# ramanPi_interfaceBoard.net
KiCad netlist of a schematic drawn in EAGLE
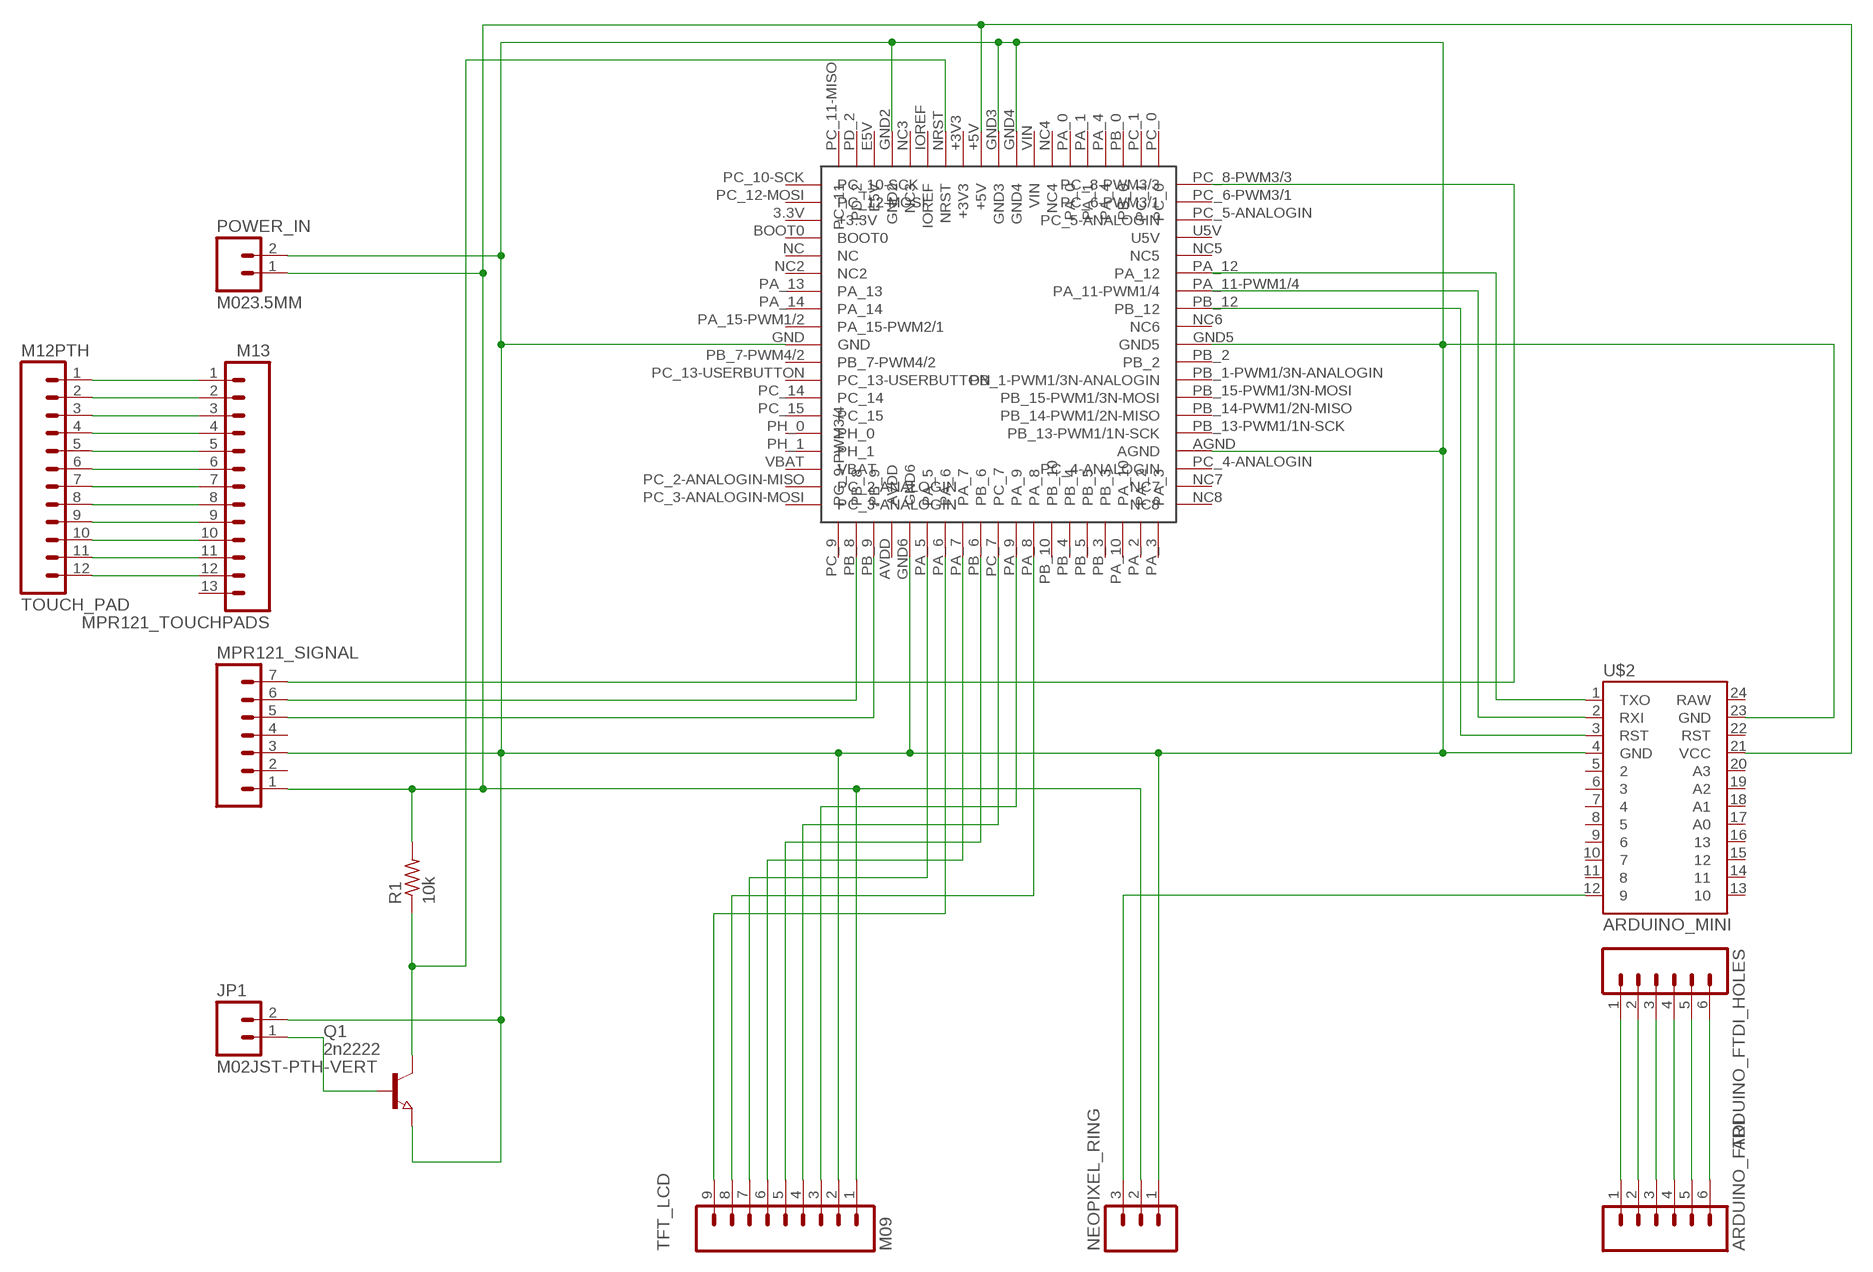
[diagram p0: schematic, sheet 1]

(export (version "E")
  (design (tool "Eeschema 10.0.6"))
  (components
    (comp (ref "ARDUINO_FTDI")
      (value "M06SIP")
      (footprint "eagle-import:1X06")
      (libsource (lib "eagle-import") (part "M06SIP"))
    )
    (comp (ref "ARDUINO_FTDI_HOLES")
      (value "M06SIP")
      (footprint "eagle-import:1X06")
      (libsource (lib "eagle-import") (part "M06SIP"))
    )
    (comp (ref "JP1")
      (value "M02JST-PTH-VERT")
      (footprint "eagle-import:JST-2-PTH-VERT")
      (libsource (lib "eagle-import") (part "M02JST-PTH-VERT"))
    )
    (comp (ref "MPR121_SIGNAL")
      (value "M07")
      (footprint "eagle-import:1X07")
      (libsource (lib "eagle-import") (part "M07"))
    )
    (comp (ref "MPR121_TOUCHPADS")
      (value "M13")
      (footprint "eagle-import:1X13")
      (libsource (lib "eagle-import") (part "M13"))
    )
    (comp (ref "NEOPIXEL_RING")
      (value "M03JST-PTH-VERT")
      (footprint "eagle-import:JST-3-PTH-VERT")
      (libsource (lib "eagle-import") (part "M03JST-PTH-VERT"))
    )
    (comp (ref "POWER_IN")
      (value "M023.5MM")
      (footprint "eagle-import:SCREWTERMINAL-3.5MM-2")
      (libsource (lib "eagle-import") (part "M023.5MM"))
    )
    (comp (ref "Q1")
      (value "2n2222")
      (footprint "eagle-import:SOT23")
      (libsource (lib "eagle-import") (part "NPN-TRANSISTOR_SOT23"))
    )
    (comp (ref "R1")
      (value "10k")
      (footprint "eagle-import:M1206")
      (libsource (lib "eagle-import") (part "R-US_M1206"))
    )
    (comp (ref "TFT_LCD")
      (value "M09")
      (footprint "eagle-import:1X09")
      (libsource (lib "eagle-import") (part "M09"))
    )
    (comp (ref "TOUCH_PAD")
      (value "M12PTH")
      (footprint "eagle-import:1X12")
      (libsource (lib "eagle-import") (part "M12PTH"))
    )
    (comp (ref "U$1")
      (value "STNUCLEOF401RE")
      (footprint "eagle-import:F401-RE")
      (libsource (lib "eagle-import") (part "STNUCLEOF401RE"))
    )
    (comp (ref "U$2")
      (value "ARDUINO_MINI")
      (footprint "eagle-import:ARDUINO_MINI")
      (libsource (lib "eagle-import") (part "ARDUINO_MINI"))
    )
  )
  (nets
    (net (code "1") (name "/+3.3V") (class "Default")
      (node (ref "U$1") (pin "3.3V") (pinfunction "+3.3V_3.3V") (pintype "power_in"))
    )
    (net (code "2") (name "/+3V3") (class "Default")
      (node (ref "U$1") (pin "+3V3") (pinfunction "+3V3_+3V3") (pintype "power_in"))
    )
    (net (code "3") (name "/AVDD") (class "Default")
      (node (ref "U$1") (pin "AVDD") (pinfunction "AVDD_AVDD") (pintype "power_in"))
    )
    (net (code "4") (name "/E5V") (class "Default")
      (node (ref "U$1") (pin "E5V") (pinfunction "E5V_E5V") (pintype "power_in"))
    )
    (net (code "5") (name "/U5V") (class "Default")
      (node (ref "U$1") (pin "U5V") (pinfunction "U5V_U5V") (pintype "power_in"))
    )
    (net (code "6") (name "/VBAT") (class "Default")
      (node (ref "U$1") (pin "VBAT") (pinfunction "VBAT_VBAT") (pintype "power_in"))
    )
    (net (code "7") (name "/VIN") (class "Default")
      (node (ref "U$1") (pin "VIN") (pinfunction "VIN_VIN") (pintype "power_in"))
    )
    (net (code "8") (name "Net-(ARDUINO_FTDI-Pad1)") (class "Default")
      (node (ref "ARDUINO_FTDI") (pin "1") (pinfunction "1_1") (pintype "passive"))
      (node (ref "ARDUINO_FTDI_HOLES") (pin "1") (pinfunction "1_1") (pintype "passive"))
    )
    (net (code "9") (name "Net-(ARDUINO_FTDI-Pad2)") (class "Default")
      (node (ref "ARDUINO_FTDI") (pin "2") (pinfunction "2_2") (pintype "passive"))
      (node (ref "ARDUINO_FTDI_HOLES") (pin "2") (pinfunction "2_2") (pintype "passive"))
    )
    (net (code "10") (name "Net-(ARDUINO_FTDI-Pad3)") (class "Default")
      (node (ref "ARDUINO_FTDI") (pin "3") (pinfunction "3_3") (pintype "passive"))
      (node (ref "ARDUINO_FTDI_HOLES") (pin "3") (pinfunction "3_3") (pintype "passive"))
    )
    (net (code "11") (name "Net-(ARDUINO_FTDI-Pad4)") (class "Default")
      (node (ref "ARDUINO_FTDI") (pin "4") (pinfunction "4_4") (pintype "passive"))
      (node (ref "ARDUINO_FTDI_HOLES") (pin "4") (pinfunction "4_4") (pintype "passive"))
    )
    (net (code "12") (name "Net-(ARDUINO_FTDI-Pad5)") (class "Default")
      (node (ref "ARDUINO_FTDI") (pin "5") (pinfunction "5_5") (pintype "passive"))
      (node (ref "ARDUINO_FTDI_HOLES") (pin "5") (pinfunction "5_5") (pintype "passive"))
    )
    (net (code "13") (name "Net-(ARDUINO_FTDI-Pad6)") (class "Default")
      (node (ref "ARDUINO_FTDI") (pin "6") (pinfunction "6_6") (pintype "passive"))
      (node (ref "ARDUINO_FTDI_HOLES") (pin "6") (pinfunction "6_6") (pintype "passive"))
    )
    (net (code "14") (name "Net-(MPR121_SIGNAL-Pad5)") (class "Default")
      (node (ref "MPR121_SIGNAL") (pin "5") (pinfunction "5_5") (pintype "passive"))
      (node (ref "U$1") (pin "PB_9") (pinfunction "PB_9_PB_9") (pintype "bidirectional"))
    )
    (net (code "15") (name "Net-(MPR121_SIGNAL-Pad6)") (class "Default")
      (node (ref "MPR121_SIGNAL") (pin "6") (pinfunction "6_6") (pintype "passive"))
      (node (ref "U$1") (pin "PB_8") (pinfunction "PB_8_PB_8") (pintype "bidirectional"))
    )
    (net (code "16") (name "Net-(MPR121_SIGNAL-Pad7)") (class "Default")
      (node (ref "MPR121_SIGNAL") (pin "7") (pinfunction "7_7") (pintype "passive"))
      (node (ref "U$1") (pin "PC_8-PWM3/3") (pinfunction "PC_8-PWM3/3_PC_8-PWM3/3") (pintype "bidirectional"))
    )
    (net (code "17") (name "Net-(MPR121_TOUCHPADS-Pad1)") (class "Default")
      (node (ref "MPR121_TOUCHPADS") (pin "1") (pinfunction "1_1") (pintype "passive"))
      (node (ref "TOUCH_PAD") (pin "1") (pinfunction "1_1") (pintype "passive"))
    )
    (net (code "18") (name "Net-(MPR121_TOUCHPADS-Pad2)") (class "Default")
      (node (ref "MPR121_TOUCHPADS") (pin "2") (pinfunction "2_2") (pintype "passive"))
      (node (ref "TOUCH_PAD") (pin "2") (pinfunction "2_2") (pintype "passive"))
    )
    (net (code "19") (name "Net-(MPR121_TOUCHPADS-Pad3)") (class "Default")
      (node (ref "MPR121_TOUCHPADS") (pin "3") (pinfunction "3_3") (pintype "passive"))
      (node (ref "TOUCH_PAD") (pin "3") (pinfunction "3_3") (pintype "passive"))
    )
    (net (code "20") (name "Net-(MPR121_TOUCHPADS-Pad4)") (class "Default")
      (node (ref "MPR121_TOUCHPADS") (pin "4") (pinfunction "4_4") (pintype "passive"))
      (node (ref "TOUCH_PAD") (pin "4") (pinfunction "4_4") (pintype "passive"))
    )
    (net (code "21") (name "Net-(MPR121_TOUCHPADS-Pad5)") (class "Default")
      (node (ref "MPR121_TOUCHPADS") (pin "5") (pinfunction "5_5") (pintype "passive"))
      (node (ref "TOUCH_PAD") (pin "5") (pinfunction "5_5") (pintype "passive"))
    )
    (net (code "22") (name "Net-(MPR121_TOUCHPADS-Pad6)") (class "Default")
      (node (ref "MPR121_TOUCHPADS") (pin "6") (pinfunction "6_6") (pintype "passive"))
      (node (ref "TOUCH_PAD") (pin "6") (pinfunction "6_6") (pintype "passive"))
    )
    (net (code "23") (name "Net-(MPR121_TOUCHPADS-Pad7)") (class "Default")
      (node (ref "MPR121_TOUCHPADS") (pin "7") (pinfunction "7_7") (pintype "passive"))
      (node (ref "TOUCH_PAD") (pin "7") (pinfunction "7_7") (pintype "passive"))
    )
    (net (code "24") (name "Net-(MPR121_TOUCHPADS-Pad8)") (class "Default")
      (node (ref "MPR121_TOUCHPADS") (pin "8") (pinfunction "8_8") (pintype "passive"))
      (node (ref "TOUCH_PAD") (pin "8") (pinfunction "8_8") (pintype "passive"))
    )
    (net (code "25") (name "Net-(MPR121_TOUCHPADS-Pad9)") (class "Default")
      (node (ref "MPR121_TOUCHPADS") (pin "9") (pinfunction "9_9") (pintype "passive"))
      (node (ref "TOUCH_PAD") (pin "9") (pinfunction "9_9") (pintype "passive"))
    )
    (net (code "26") (name "Net-(MPR121_TOUCHPADS-Pad10)") (class "Default")
      (node (ref "MPR121_TOUCHPADS") (pin "10") (pinfunction "10_10") (pintype "passive"))
      (node (ref "TOUCH_PAD") (pin "10") (pinfunction "10_10") (pintype "passive"))
    )
    (net (code "27") (name "Net-(MPR121_TOUCHPADS-Pad11)") (class "Default")
      (node (ref "MPR121_TOUCHPADS") (pin "11") (pinfunction "11_11") (pintype "passive"))
      (node (ref "TOUCH_PAD") (pin "11") (pinfunction "11_11") (pintype "passive"))
    )
    (net (code "28") (name "Net-(MPR121_TOUCHPADS-Pad12)") (class "Default")
      (node (ref "MPR121_TOUCHPADS") (pin "12") (pinfunction "12_12") (pintype "passive"))
      (node (ref "TOUCH_PAD") (pin "12") (pinfunction "12_12") (pintype "passive"))
    )
    (net (code "29") (name "Net-(Q1-B)") (class "Default")
      (node (ref "JP1") (pin "1") (pinfunction "1_1") (pintype "passive"))
      (node (ref "Q1") (pin "1") (pinfunction "B_1") (pintype "passive"))
    )
    (net (code "30") (name "Net-(Q1-C)") (class "Default")
      (node (ref "Q1") (pin "3") (pinfunction "C_3") (pintype "passive"))
      (node (ref "R1") (pin "1") (pinfunction "1_1") (pintype "passive"))
      (node (ref "U$1") (pin "NRST") (pinfunction "NRST_NRST") (pintype "bidirectional"))
    )
    (net (code "31") (name "Net-(Q1-E)") (class "Default")
      (node (ref "JP1") (pin "2") (pinfunction "2_2") (pintype "passive"))
      (node (ref "MPR121_SIGNAL") (pin "3") (pinfunction "3_3") (pintype "passive"))
      (node (ref "NEOPIXEL_RING") (pin "1") (pinfunction "1_1") (pintype "passive"))
      (node (ref "POWER_IN") (pin "2") (pinfunction "2_2") (pintype "passive"))
      (node (ref "Q1") (pin "2") (pinfunction "E_2") (pintype "passive"))
      (node (ref "TFT_LCD") (pin "2") (pinfunction "2_2") (pintype "passive"))
      (node (ref "U$1") (pin "AGND") (pinfunction "AGND_AGND") (pintype "power_in"))
      (node (ref "U$1") (pin "GND") (pinfunction "GND_GND") (pintype "power_in"))
      (node (ref "U$1") (pin "GND2") (pinfunction "GND2_GND2") (pintype "power_in"))
      (node (ref "U$1") (pin "GND3") (pinfunction "GND3_GND3") (pintype "power_in"))
      (node (ref "U$1") (pin "GND4") (pinfunction "GND4_GND4") (pintype "power_in"))
      (node (ref "U$1") (pin "GND5") (pinfunction "GND5_GND5") (pintype "power_in"))
      (node (ref "U$1") (pin "GND6") (pinfunction "GND6_GND6") (pintype "power_in"))
      (node (ref "U$2") (pin "23") (pinfunction "GND_23") (pintype "bidirectional"))
      (node (ref "U$2") (pin "4") (pinfunction "GND_4") (pintype "bidirectional"))
    )
    (net (code "32") (name "Net-(TFT_LCD-Pad3)") (class "Default")
      (node (ref "TFT_LCD") (pin "3") (pinfunction "3_3") (pintype "passive"))
      (node (ref "U$1") (pin "PA_9") (pinfunction "PA_9_PA_9") (pintype "bidirectional"))
    )
    (net (code "33") (name "Net-(TFT_LCD-Pad4)") (class "Default")
      (node (ref "TFT_LCD") (pin "4") (pinfunction "4_4") (pintype "passive"))
      (node (ref "U$1") (pin "PC_7") (pinfunction "PC_7_PC_7") (pintype "bidirectional"))
    )
    (net (code "34") (name "Net-(TFT_LCD-Pad5)") (class "Default")
      (node (ref "TFT_LCD") (pin "5") (pinfunction "5_5") (pintype "passive"))
      (node (ref "U$1") (pin "PB_6") (pinfunction "PB_6_PB_6") (pintype "bidirectional"))
    )
    (net (code "35") (name "Net-(TFT_LCD-Pad6)") (class "Default")
      (node (ref "TFT_LCD") (pin "6") (pinfunction "6_6") (pintype "passive"))
      (node (ref "U$1") (pin "PA_7") (pinfunction "PA_7_PA_7") (pintype "bidirectional"))
    )
    (net (code "36") (name "Net-(TFT_LCD-Pad7)") (class "Default")
      (node (ref "TFT_LCD") (pin "7") (pinfunction "7_7") (pintype "passive"))
      (node (ref "U$1") (pin "PA_5") (pinfunction "PA_5_PA_5") (pintype "bidirectional"))
    )
    (net (code "37") (name "Net-(TFT_LCD-Pad8)") (class "Default")
      (node (ref "TFT_LCD") (pin "8") (pinfunction "8_8") (pintype "passive"))
      (node (ref "U$1") (pin "PA_8") (pinfunction "PA_8_PA_8") (pintype "bidirectional"))
    )
    (net (code "38") (name "Net-(TFT_LCD-Pad9)") (class "Default")
      (node (ref "TFT_LCD") (pin "9") (pinfunction "9_9") (pintype "passive"))
      (node (ref "U$1") (pin "PA_6") (pinfunction "PA_6_PA_6") (pintype "bidirectional"))
    )
    (net (code "39") (name "Net-(U$1-PadPB_12)") (class "Default")
      (node (ref "U$1") (pin "PB_12") (pinfunction "PB_12_PB_12") (pintype "bidirectional"))
      (node (ref "U$2") (pin "3") (pinfunction "RST_3") (pintype "bidirectional"))
    )
    (net (code "40") (name "Net-(U$2-9)") (class "Default")
      (node (ref "NEOPIXEL_RING") (pin "3") (pinfunction "3_3") (pintype "passive"))
      (node (ref "U$2") (pin "12") (pinfunction "9_12") (pintype "bidirectional"))
    )
    (net (code "41") (name "Net-(U$2-RXI)") (class "Default")
      (node (ref "U$1") (pin "PA_11-PWM1/4") (pinfunction "PA_11-PWM1/4_PA_11-PWM1/4") (pintype "bidirectional"))
      (node (ref "U$2") (pin "2") (pinfunction "RXI_2") (pintype "bidirectional"))
    )
    (net (code "42") (name "Net-(U$2-TXO)") (class "Default")
      (node (ref "U$1") (pin "PA_12") (pinfunction "PA_12_PA_12") (pintype "bidirectional"))
      (node (ref "U$2") (pin "1") (pinfunction "TXO_1") (pintype "bidirectional"))
    )
    (net (code "43") (name "Net-(U$2-VCC)") (class "Default")
      (node (ref "MPR121_SIGNAL") (pin "1") (pinfunction "1_1") (pintype "passive"))
      (node (ref "NEOPIXEL_RING") (pin "2") (pinfunction "2_2") (pintype "passive"))
      (node (ref "POWER_IN") (pin "1") (pinfunction "1_1") (pintype "passive"))
      (node (ref "R1") (pin "2") (pinfunction "2_2") (pintype "passive"))
      (node (ref "TFT_LCD") (pin "1") (pinfunction "1_1") (pintype "passive"))
      (node (ref "U$1") (pin "+5V") (pinfunction "+5V_+5V") (pintype "power_in"))
      (node (ref "U$2") (pin "21") (pinfunction "VCC_21") (pintype "bidirectional"))
    )
    (net (code "44") (name "unconnected-(MPR121_SIGNAL-Pad2)") (class "Default")
      (node (ref "MPR121_SIGNAL") (pin "2") (pinfunction "2_2") (pintype "passive"))
    )
    (net (code "45") (name "unconnected-(MPR121_SIGNAL-Pad4)") (class "Default")
      (node (ref "MPR121_SIGNAL") (pin "4") (pinfunction "4_4") (pintype "passive"))
    )
    (net (code "46") (name "unconnected-(MPR121_TOUCHPADS-Pad13)") (class "Default")
      (node (ref "MPR121_TOUCHPADS") (pin "13") (pinfunction "13_13") (pintype "passive"))
    )
    (net (code "47") (name "unconnected-(U$1-PA_15-PWM2{slash}1-PadPA_15-PWM1{slash}2)") (class "Default")
      (node (ref "U$1") (pin "PA_15-PWM1/2") (pinfunction "PA_15-PWM2/1_PA_15-PWM1/2") (pintype "bidirectional"))
    )
    (net (code "48") (name "unconnected-(U$1-PC_2-ANALOGIN-PadPC_2-ANALOGIN-MISO)") (class "Default")
      (node (ref "U$1") (pin "PC_2-ANALOGIN-MISO") (pinfunction "PC_2-ANALOGIN_PC_2-ANALOGIN-MISO") (pintype "bidirectional"))
    )
    (net (code "49") (name "unconnected-(U$1-PC_3-ANALOGIN-PadPC_3-ANALOGIN-MOSI)") (class "Default")
      (node (ref "U$1") (pin "PC_3-ANALOGIN-MOSI") (pinfunction "PC_3-ANALOGIN_PC_3-ANALOGIN-MOSI") (pintype "bidirectional"))
    )
    (net (code "50") (name "unconnected-(U$1-PC_9-PWM3{slash}4-PadPC_9)") (class "Default")
      (node (ref "U$1") (pin "PC_9") (pinfunction "PC_9-PWM3/4_PC_9") (pintype "bidirectional"))
    )
    (net (code "51") (name "unconnected-(U$1-PC_11-PadPC_11-MISO)") (class "Default")
      (node (ref "U$1") (pin "PC_11-MISO") (pinfunction "PC_11_PC_11-MISO") (pintype "bidirectional"))
    )
    (net (code "52") (name "unconnected-(U$1-PadBOOT0)") (class "Default")
      (node (ref "U$1") (pin "BOOT0") (pinfunction "BOOT0_BOOT0") (pintype "bidirectional"))
    )
    (net (code "53") (name "unconnected-(U$1-PadIOREF)") (class "Default")
      (node (ref "U$1") (pin "IOREF") (pinfunction "IOREF_IOREF") (pintype "bidirectional"))
    )
    (net (code "54") (name "unconnected-(U$1-PadNC)") (class "Default")
      (node (ref "U$1") (pin "NC") (pinfunction "NC_NC") (pintype "no_connect"))
    )
    (net (code "55") (name "unconnected-(U$1-PadNC2)") (class "Default")
      (node (ref "U$1") (pin "NC2") (pinfunction "NC2_NC2") (pintype "no_connect"))
    )
    (net (code "56") (name "unconnected-(U$1-PadNC3)") (class "Default")
      (node (ref "U$1") (pin "NC3") (pinfunction "NC3_NC3") (pintype "no_connect"))
    )
    (net (code "57") (name "unconnected-(U$1-PadNC4)") (class "Default")
      (node (ref "U$1") (pin "NC4") (pinfunction "NC4_NC4") (pintype "bidirectional"))
    )
    (net (code "58") (name "unconnected-(U$1-PadNC5)") (class "Default")
      (node (ref "U$1") (pin "NC5") (pinfunction "NC5_NC5") (pintype "no_connect"))
    )
    (net (code "59") (name "unconnected-(U$1-PadNC6)") (class "Default")
      (node (ref "U$1") (pin "NC6") (pinfunction "NC6_NC6") (pintype "no_connect"))
    )
    (net (code "60") (name "unconnected-(U$1-PadNC7)") (class "Default")
      (node (ref "U$1") (pin "NC7") (pinfunction "NC7_NC7") (pintype "bidirectional"))
    )
    (net (code "61") (name "unconnected-(U$1-PadNC8)") (class "Default")
      (node (ref "U$1") (pin "NC8") (pinfunction "NC8_NC8") (pintype "bidirectional"))
    )
    (net (code "62") (name "unconnected-(U$1-PadPA_0)") (class "Default")
      (node (ref "U$1") (pin "PA_0") (pinfunction "PA_0_PA_0") (pintype "bidirectional"))
    )
    (net (code "63") (name "unconnected-(U$1-PadPA_1)") (class "Default")
      (node (ref "U$1") (pin "PA_1") (pinfunction "PA_1_PA_1") (pintype "bidirectional"))
    )
    (net (code "64") (name "unconnected-(U$1-PadPA_2)") (class "Default")
      (node (ref "U$1") (pin "PA_2") (pinfunction "PA_2_PA_2") (pintype "bidirectional"))
    )
    (net (code "65") (name "unconnected-(U$1-PadPA_3)") (class "Default")
      (node (ref "U$1") (pin "PA_3") (pinfunction "PA_3_PA_3") (pintype "bidirectional"))
    )
    (net (code "66") (name "unconnected-(U$1-PadPA_4)") (class "Default")
      (node (ref "U$1") (pin "PA_4") (pinfunction "PA_4_PA_4") (pintype "bidirectional"))
    )
    (net (code "67") (name "unconnected-(U$1-PadPA_10)") (class "Default")
      (node (ref "U$1") (pin "PA_10") (pinfunction "PA_10_PA_10") (pintype "bidirectional"))
    )
    (net (code "68") (name "unconnected-(U$1-PadPA_13)") (class "Default")
      (node (ref "U$1") (pin "PA_13") (pinfunction "PA_13_PA_13") (pintype "bidirectional"))
    )
    (net (code "69") (name "unconnected-(U$1-PadPA_14)") (class "Default")
      (node (ref "U$1") (pin "PA_14") (pinfunction "PA_14_PA_14") (pintype "bidirectional"))
    )
    (net (code "70") (name "unconnected-(U$1-PadPB_0)") (class "Default")
      (node (ref "U$1") (pin "PB_0") (pinfunction "PB_0_PB_0") (pintype "bidirectional"))
    )
    (net (code "71") (name "unconnected-(U$1-PadPB_1-PWM1{slash}3N-ANALOGIN)") (class "Default")
      (node (ref "U$1") (pin "PB_1-PWM1/3N-ANALOGIN") (pinfunction "PB_1-PWM1/3N-ANALOGIN_PB_1-PWM1/3N-ANALOGIN") (pintype "bidirectional"))
    )
    (net (code "72") (name "unconnected-(U$1-PadPB_2)") (class "Default")
      (node (ref "U$1") (pin "PB_2") (pinfunction "PB_2_PB_2") (pintype "bidirectional"))
    )
    (net (code "73") (name "unconnected-(U$1-PadPB_3)") (class "Default")
      (node (ref "U$1") (pin "PB_3") (pinfunction "PB_3_PB_3") (pintype "bidirectional"))
    )
    (net (code "74") (name "unconnected-(U$1-PadPB_4)") (class "Default")
      (node (ref "U$1") (pin "PB_4") (pinfunction "PB_4_PB_4") (pintype "bidirectional"))
    )
    (net (code "75") (name "unconnected-(U$1-PadPB_5)") (class "Default")
      (node (ref "U$1") (pin "PB_5") (pinfunction "PB_5_PB_5") (pintype "bidirectional"))
    )
    (net (code "76") (name "unconnected-(U$1-PadPB_7-PWM4{slash}2)") (class "Default")
      (node (ref "U$1") (pin "PB_7-PWM4/2") (pinfunction "PB_7-PWM4/2_PB_7-PWM4/2") (pintype "bidirectional"))
    )
    (net (code "77") (name "unconnected-(U$1-PadPB_10)") (class "Default")
      (node (ref "U$1") (pin "PB_10") (pinfunction "PB_10_PB_10") (pintype "bidirectional"))
    )
    (net (code "78") (name "unconnected-(U$1-PadPB_13-PWM1{slash}1N-SCK)") (class "Default")
      (node (ref "U$1") (pin "PB_13-PWM1/1N-SCK") (pinfunction "PB_13-PWM1/1N-SCK_PB_13-PWM1/1N-SCK") (pintype "bidirectional"))
    )
    (net (code "79") (name "unconnected-(U$1-PadPB_14-PWM1{slash}2N-MISO)") (class "Default")
      (node (ref "U$1") (pin "PB_14-PWM1/2N-MISO") (pinfunction "PB_14-PWM1/2N-MISO_PB_14-PWM1/2N-MISO") (pintype "bidirectional"))
    )
    (net (code "80") (name "unconnected-(U$1-PadPB_15-PWM1{slash}3N-MOSI)") (class "Default")
      (node (ref "U$1") (pin "PB_15-PWM1/3N-MOSI") (pinfunction "PB_15-PWM1/3N-MOSI_PB_15-PWM1/3N-MOSI") (pintype "bidirectional"))
    )
    (net (code "81") (name "unconnected-(U$1-PadPC_0)") (class "Default")
      (node (ref "U$1") (pin "PC_0") (pinfunction "PC_0_PC_0") (pintype "bidirectional"))
    )
    (net (code "82") (name "unconnected-(U$1-PadPC_1)") (class "Default")
      (node (ref "U$1") (pin "PC_1") (pinfunction "PC_1_PC_1") (pintype "bidirectional"))
    )
    (net (code "83") (name "unconnected-(U$1-PadPC_4-ANALOGIN)") (class "Default")
      (node (ref "U$1") (pin "PC_4-ANALOGIN") (pinfunction "PC_4-ANALOGIN_PC_4-ANALOGIN") (pintype "bidirectional"))
    )
    (net (code "84") (name "unconnected-(U$1-PadPC_5-ANALOGIN)") (class "Default")
      (node (ref "U$1") (pin "PC_5-ANALOGIN") (pinfunction "PC_5-ANALOGIN_PC_5-ANALOGIN") (pintype "bidirectional"))
    )
    (net (code "85") (name "unconnected-(U$1-PadPC_6-PWM3{slash}1)") (class "Default")
      (node (ref "U$1") (pin "PC_6-PWM3/1") (pinfunction "PC_6-PWM3/1_PC_6-PWM3/1") (pintype "bidirectional"))
    )
    (net (code "86") (name "unconnected-(U$1-PadPC_10-SCK)") (class "Default")
      (node (ref "U$1") (pin "PC_10-SCK") (pinfunction "PC_10-SCK_PC_10-SCK") (pintype "bidirectional"))
    )
    (net (code "87") (name "unconnected-(U$1-PadPC_12-MOSI)") (class "Default")
      (node (ref "U$1") (pin "PC_12-MOSI") (pinfunction "PC_12-MOSI_PC_12-MOSI") (pintype "bidirectional"))
    )
    (net (code "88") (name "unconnected-(U$1-PadPC_13-USERBUTTON)") (class "Default")
      (node (ref "U$1") (pin "PC_13-USERBUTTON") (pinfunction "PC_13-USERBUTTON_PC_13-USERBUTTON") (pintype "bidirectional"))
    )
    (net (code "89") (name "unconnected-(U$1-PadPC_14)") (class "Default")
      (node (ref "U$1") (pin "PC_14") (pinfunction "PC_14_PC_14") (pintype "bidirectional"))
    )
    (net (code "90") (name "unconnected-(U$1-PadPC_15)") (class "Default")
      (node (ref "U$1") (pin "PC_15") (pinfunction "PC_15_PC_15") (pintype "bidirectional"))
    )
    (net (code "91") (name "unconnected-(U$1-PadPD_2)") (class "Default")
      (node (ref "U$1") (pin "PD_2") (pinfunction "PD_2_PD_2") (pintype "bidirectional"))
    )
    (net (code "92") (name "unconnected-(U$1-PadPH_0)") (class "Default")
      (node (ref "U$1") (pin "PH_0") (pinfunction "PH_0_PH_0") (pintype "bidirectional"))
    )
    (net (code "93") (name "unconnected-(U$1-PadPH_1)") (class "Default")
      (node (ref "U$1") (pin "PH_1") (pinfunction "PH_1_PH_1") (pintype "bidirectional"))
    )
    (net (code "94") (name "unconnected-(U$2-2-Pad5)") (class "Default")
      (node (ref "U$2") (pin "5") (pinfunction "2_5") (pintype "bidirectional"))
    )
    (net (code "95") (name "unconnected-(U$2-3-Pad6)") (class "Default")
      (node (ref "U$2") (pin "6") (pinfunction "3_6") (pintype "bidirectional"))
    )
    (net (code "96") (name "unconnected-(U$2-4-Pad7)") (class "Default")
      (node (ref "U$2") (pin "7") (pinfunction "4_7") (pintype "bidirectional"))
    )
    (net (code "97") (name "unconnected-(U$2-5-Pad8)") (class "Default")
      (node (ref "U$2") (pin "8") (pinfunction "5_8") (pintype "bidirectional"))
    )
    (net (code "98") (name "unconnected-(U$2-6-Pad9)") (class "Default")
      (node (ref "U$2") (pin "9") (pinfunction "6_9") (pintype "bidirectional"))
    )
    (net (code "99") (name "unconnected-(U$2-7-Pad10)") (class "Default")
      (node (ref "U$2") (pin "10") (pinfunction "7_10") (pintype "bidirectional"))
    )
    (net (code "100") (name "unconnected-(U$2-8-Pad11)") (class "Default")
      (node (ref "U$2") (pin "11") (pinfunction "8_11") (pintype "bidirectional"))
    )
    (net (code "101") (name "unconnected-(U$2-10-Pad13)") (class "Default")
      (node (ref "U$2") (pin "13") (pinfunction "10_13") (pintype "bidirectional"))
    )
    (net (code "102") (name "unconnected-(U$2-11-Pad14)") (class "Default")
      (node (ref "U$2") (pin "14") (pinfunction "11_14") (pintype "bidirectional"))
    )
    (net (code "103") (name "unconnected-(U$2-12-Pad15)") (class "Default")
      (node (ref "U$2") (pin "15") (pinfunction "12_15") (pintype "bidirectional"))
    )
    (net (code "104") (name "unconnected-(U$2-13-Pad16)") (class "Default")
      (node (ref "U$2") (pin "16") (pinfunction "13_16") (pintype "bidirectional"))
    )
    (net (code "105") (name "unconnected-(U$2-A0-Pad17)") (class "Default")
      (node (ref "U$2") (pin "17") (pinfunction "A0_17") (pintype "bidirectional"))
    )
    (net (code "106") (name "unconnected-(U$2-A1-Pad18)") (class "Default")
      (node (ref "U$2") (pin "18") (pinfunction "A1_18") (pintype "bidirectional"))
    )
    (net (code "107") (name "unconnected-(U$2-A2-Pad19)") (class "Default")
      (node (ref "U$2") (pin "19") (pinfunction "A2_19") (pintype "bidirectional"))
    )
    (net (code "108") (name "unconnected-(U$2-A3-Pad20)") (class "Default")
      (node (ref "U$2") (pin "20") (pinfunction "A3_20") (pintype "bidirectional"))
    )
    (net (code "109") (name "unconnected-(U$2-RAW-Pad24)") (class "Default")
      (node (ref "U$2") (pin "24") (pinfunction "RAW_24") (pintype "bidirectional"))
    )
    (net (code "110") (name "unconnected-(U$2-RST-Pad22)") (class "Default")
      (node (ref "U$2") (pin "22") (pinfunction "RST_22") (pintype "bidirectional"))
    )
  )
)
